# emonTx4-CTExt.net
KiCad netlist of a schematic drawn in EAGLE
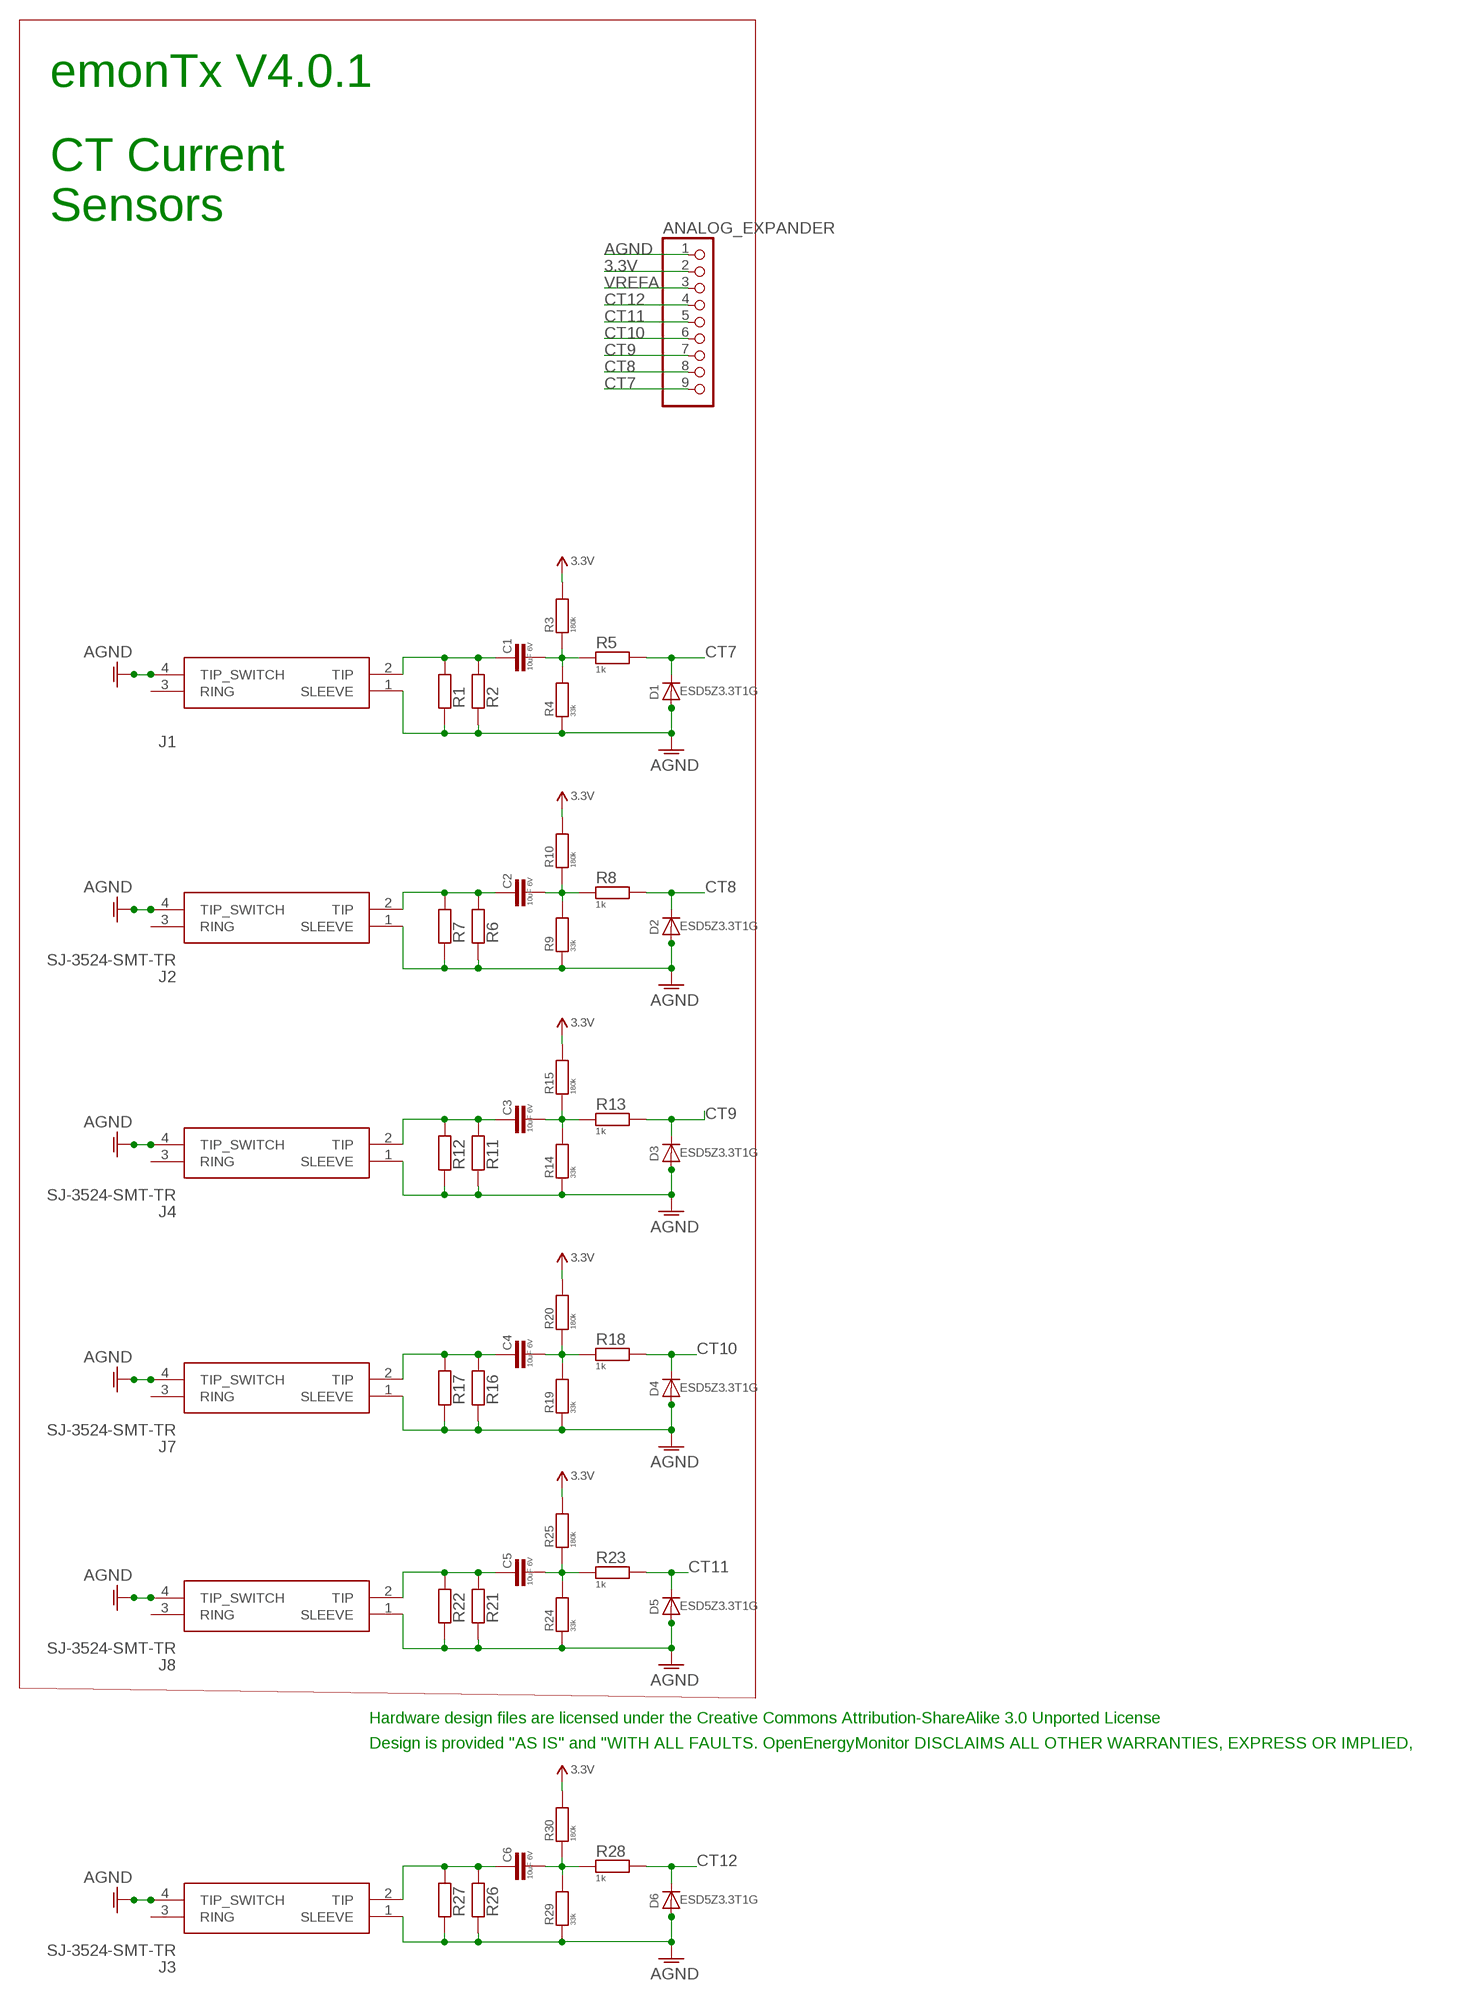
[diagram p0: schematic, sheet 1]

(export (version "E")
  (design (tool "Eeschema 10.0.6"))
  (components
    (comp (ref "ANALOG_EXPANDER")
      (value "PINHD-1X9")
      (footprint "eagle-import:1X09-BIG")
      (libsource (lib "eagle-import") (part "PINHD-1X9"))
    )
    (comp (ref "C1")
      (value "10uF 6V")
      (footprint "eagle-import:C0603")
      (libsource (lib "eagle-import") (part "C-EUC0603"))
    )
    (comp (ref "C2")
      (value "10uF 6V")
      (footprint "eagle-import:C0603")
      (libsource (lib "eagle-import") (part "C-EUC0603"))
    )
    (comp (ref "C3")
      (value "10uF 6V")
      (footprint "eagle-import:C0603")
      (libsource (lib "eagle-import") (part "C-EUC0603"))
    )
    (comp (ref "C4")
      (value "10uF 6V")
      (footprint "eagle-import:C0603")
      (libsource (lib "eagle-import") (part "C-EUC0603"))
    )
    (comp (ref "C5")
      (value "10uF 6V")
      (footprint "eagle-import:C0603")
      (libsource (lib "eagle-import") (part "C-EUC0603"))
    )
    (comp (ref "C6")
      (value "10uF 6V")
      (footprint "eagle-import:C0603")
      (libsource (lib "eagle-import") (part "C-EUC0603"))
    )
    (comp (ref "D1")
      (value "ESD5Z3.3T1G")
      (footprint "eagle-import:SOD-523")
      (libsource (lib "eagle-import") (part "DIODESOD-523"))
    )
    (comp (ref "D2")
      (value "ESD5Z3.3T1G")
      (footprint "eagle-import:SOD-523")
      (libsource (lib "eagle-import") (part "DIODESOD-523"))
    )
    (comp (ref "D3")
      (value "ESD5Z3.3T1G")
      (footprint "eagle-import:SOD-523")
      (libsource (lib "eagle-import") (part "DIODESOD-523"))
    )
    (comp (ref "D4")
      (value "ESD5Z3.3T1G")
      (footprint "eagle-import:SOD-523")
      (libsource (lib "eagle-import") (part "DIODESOD-523"))
    )
    (comp (ref "D5")
      (value "ESD5Z3.3T1G")
      (footprint "eagle-import:SOD-523")
      (libsource (lib "eagle-import") (part "DIODESOD-523"))
    )
    (comp (ref "D6")
      (value "ESD5Z3.3T1G")
      (footprint "eagle-import:SOD-523")
      (libsource (lib "eagle-import") (part "DIODESOD-523"))
    )
    (comp (ref "J1")
      (value "SJ-3524-SMT-TR")
      (footprint "eagle-import:SJ-3524-SMT-TR")
      (fields (field (name "MOUSER_PART_NUMBER") "490-SJ-3524-SMT-TR"))
      (libsource (lib "eagle-import") (part "SJ-3524-SMT-TR"))
    )
    (comp (ref "J2")
      (value "SJ-3524-SMT-TR")
      (footprint "eagle-import:SJ-3524-SMT-TR")
      (fields (field (name "MOUSER_PART_NUMBER") "490-SJ-3524-SMT-TR"))
      (libsource (lib "eagle-import") (part "SJ-3524-SMT-TR"))
    )
    (comp (ref "J3")
      (value "SJ-3524-SMT-TR")
      (footprint "eagle-import:SJ-3524-SMT-TR")
      (fields (field (name "MOUSER_PART_NUMBER") "490-SJ-3524-SMT-TR"))
      (libsource (lib "eagle-import") (part "SJ-3524-SMT-TR"))
    )
    (comp (ref "J4")
      (value "SJ-3524-SMT-TR")
      (footprint "eagle-import:SJ-3524-SMT-TR")
      (fields (field (name "MOUSER_PART_NUMBER") "490-SJ-3524-SMT-TR"))
      (libsource (lib "eagle-import") (part "SJ-3524-SMT-TR"))
    )
    (comp (ref "J7")
      (value "SJ-3524-SMT-TR")
      (footprint "eagle-import:SJ-3524-SMT-TR")
      (fields (field (name "MOUSER_PART_NUMBER") "490-SJ-3524-SMT-TR"))
      (libsource (lib "eagle-import") (part "SJ-3524-SMT-TR"))
    )
    (comp (ref "J8")
      (value "SJ-3524-SMT-TR")
      (footprint "eagle-import:SJ-3524-SMT-TR")
      (fields (field (name "MOUSER_PART_NUMBER") "490-SJ-3524-SMT-TR"))
      (libsource (lib "eagle-import") (part "SJ-3524-SMT-TR"))
    )
    (comp (ref "R1")
      (value "R-EU_R1206")
      (footprint "eagle-import:R1206")
      (libsource (lib "eagle-import") (part "R-EU_R1206"))
    )
    (comp (ref "R2")
      (value "R-EU_0204/7")
      (footprint "eagle-import:0204_7")
      (libsource (lib "eagle-import") (part "R-EU_0204/7"))
    )
    (comp (ref "R3")
      (value "180k")
      (footprint "eagle-import:R0603")
      (libsource (lib "eagle-import") (part "R-EU_R0603"))
    )
    (comp (ref "R4")
      (value "33k")
      (footprint "eagle-import:R0603")
      (libsource (lib "eagle-import") (part "R-EU_R0603"))
    )
    (comp (ref "R5")
      (value "1k")
      (footprint "eagle-import:R0603")
      (libsource (lib "eagle-import") (part "R-EU_R0603"))
    )
    (comp (ref "R6")
      (value "R-EU_0204/7")
      (footprint "eagle-import:0204_7")
      (libsource (lib "eagle-import") (part "R-EU_0204/7"))
    )
    (comp (ref "R7")
      (value "R-EU_R1206")
      (footprint "eagle-import:R1206")
      (libsource (lib "eagle-import") (part "R-EU_R1206"))
    )
    (comp (ref "R8")
      (value "1k")
      (footprint "eagle-import:R0603")
      (libsource (lib "eagle-import") (part "R-EU_R0603"))
    )
    (comp (ref "R9")
      (value "33k")
      (footprint "eagle-import:R0603")
      (libsource (lib "eagle-import") (part "R-EU_R0603"))
    )
    (comp (ref "R10")
      (value "180k")
      (footprint "eagle-import:R0603")
      (libsource (lib "eagle-import") (part "R-EU_R0603"))
    )
    (comp (ref "R11")
      (value "R-EU_0204/7")
      (footprint "eagle-import:0204_7")
      (libsource (lib "eagle-import") (part "R-EU_0204/7"))
    )
    (comp (ref "R12")
      (value "R-EU_R1206")
      (footprint "eagle-import:R1206")
      (libsource (lib "eagle-import") (part "R-EU_R1206"))
    )
    (comp (ref "R13")
      (value "1k")
      (footprint "eagle-import:R0603")
      (libsource (lib "eagle-import") (part "R-EU_R0603"))
    )
    (comp (ref "R14")
      (value "33k")
      (footprint "eagle-import:R0603")
      (libsource (lib "eagle-import") (part "R-EU_R0603"))
    )
    (comp (ref "R15")
      (value "180k")
      (footprint "eagle-import:R0603")
      (libsource (lib "eagle-import") (part "R-EU_R0603"))
    )
    (comp (ref "R16")
      (value "R-EU_0204/7")
      (footprint "eagle-import:0204_7")
      (libsource (lib "eagle-import") (part "R-EU_0204/7"))
    )
    (comp (ref "R17")
      (value "R-EU_R1206")
      (footprint "eagle-import:R1206")
      (libsource (lib "eagle-import") (part "R-EU_R1206"))
    )
    (comp (ref "R18")
      (value "1k")
      (footprint "eagle-import:R0603")
      (libsource (lib "eagle-import") (part "R-EU_R0603"))
    )
    (comp (ref "R19")
      (value "33k")
      (footprint "eagle-import:R0603")
      (libsource (lib "eagle-import") (part "R-EU_R0603"))
    )
    (comp (ref "R20")
      (value "180k")
      (footprint "eagle-import:R0603")
      (libsource (lib "eagle-import") (part "R-EU_R0603"))
    )
    (comp (ref "R21")
      (value "R-EU_0204/7")
      (footprint "eagle-import:0204_7")
      (libsource (lib "eagle-import") (part "R-EU_0204/7"))
    )
    (comp (ref "R22")
      (value "R-EU_R1206")
      (footprint "eagle-import:R1206")
      (libsource (lib "eagle-import") (part "R-EU_R1206"))
    )
    (comp (ref "R23")
      (value "1k")
      (footprint "eagle-import:R0603")
      (libsource (lib "eagle-import") (part "R-EU_R0603"))
    )
    (comp (ref "R24")
      (value "33k")
      (footprint "eagle-import:R0603")
      (libsource (lib "eagle-import") (part "R-EU_R0603"))
    )
    (comp (ref "R25")
      (value "180k")
      (footprint "eagle-import:R0603")
      (libsource (lib "eagle-import") (part "R-EU_R0603"))
    )
    (comp (ref "R26")
      (value "R-EU_0204/7")
      (footprint "eagle-import:0204_7")
      (libsource (lib "eagle-import") (part "R-EU_0204/7"))
    )
    (comp (ref "R27")
      (value "R-EU_R1206")
      (footprint "eagle-import:R1206")
      (libsource (lib "eagle-import") (part "R-EU_R1206"))
    )
    (comp (ref "R28")
      (value "1k")
      (footprint "eagle-import:R0603")
      (libsource (lib "eagle-import") (part "R-EU_R0603"))
    )
    (comp (ref "R29")
      (value "33k")
      (footprint "eagle-import:R0603")
      (libsource (lib "eagle-import") (part "R-EU_R0603"))
    )
    (comp (ref "R30")
      (value "180k")
      (footprint "eagle-import:R0603")
      (libsource (lib "eagle-import") (part "R-EU_R0603"))
    )
  )
  (nets
    (net (code "1") (name "/CT7") (class "Default")
      (node (ref "ANALOG_EXPANDER") (pin "9") (pinfunction "9_9") (pintype "passive"))
      (node (ref "D1") (pin "K") (pinfunction "C_K") (pintype "passive"))
      (node (ref "R5") (pin "2") (pinfunction "2_2") (pintype "passive"))
    )
    (net (code "2") (name "/CT8") (class "Default")
      (node (ref "ANALOG_EXPANDER") (pin "8") (pinfunction "8_8") (pintype "passive"))
      (node (ref "D2") (pin "K") (pinfunction "C_K") (pintype "passive"))
      (node (ref "R8") (pin "2") (pinfunction "2_2") (pintype "passive"))
    )
    (net (code "3") (name "/CT9") (class "Default")
      (node (ref "ANALOG_EXPANDER") (pin "7") (pinfunction "7_7") (pintype "passive"))
      (node (ref "D3") (pin "K") (pinfunction "C_K") (pintype "passive"))
      (node (ref "R13") (pin "2") (pinfunction "2_2") (pintype "passive"))
    )
    (net (code "4") (name "/CT10") (class "Default")
      (node (ref "ANALOG_EXPANDER") (pin "6") (pinfunction "6_6") (pintype "passive"))
      (node (ref "D4") (pin "K") (pinfunction "C_K") (pintype "passive"))
      (node (ref "R18") (pin "2") (pinfunction "2_2") (pintype "passive"))
    )
    (net (code "5") (name "/CT11") (class "Default")
      (node (ref "ANALOG_EXPANDER") (pin "5") (pinfunction "5_5") (pintype "passive"))
      (node (ref "D5") (pin "K") (pinfunction "C_K") (pintype "passive"))
      (node (ref "R23") (pin "2") (pinfunction "2_2") (pintype "passive"))
    )
    (net (code "6") (name "/CT12") (class "Default")
      (node (ref "ANALOG_EXPANDER") (pin "4") (pinfunction "4_4") (pintype "passive"))
      (node (ref "D6") (pin "K") (pinfunction "C_K") (pintype "passive"))
      (node (ref "R28") (pin "2") (pinfunction "2_2") (pintype "passive"))
    )
    (net (code "7") (name "/VREFA") (class "Default")
      (node (ref "ANALOG_EXPANDER") (pin "3") (pinfunction "3_3") (pintype "passive"))
    )
    (net (code "8") (name "3.3V") (class "Default")
      (node (ref "ANALOG_EXPANDER") (pin "2") (pinfunction "2_2") (pintype "passive"))
      (node (ref "R10") (pin "2") (pinfunction "2_2") (pintype "passive"))
      (node (ref "R15") (pin "2") (pinfunction "2_2") (pintype "passive"))
      (node (ref "R20") (pin "2") (pinfunction "2_2") (pintype "passive"))
      (node (ref "R25") (pin "2") (pinfunction "2_2") (pintype "passive"))
      (node (ref "R3") (pin "2") (pinfunction "2_2") (pintype "passive"))
      (node (ref "R30") (pin "2") (pinfunction "2_2") (pintype "passive"))
    )
    (net (code "9") (name "AGND") (class "Default")
      (node (ref "ANALOG_EXPANDER") (pin "1") (pinfunction "1_1") (pintype "passive"))
      (node (ref "D1") (pin "A") (pinfunction "A_A") (pintype "passive"))
      (node (ref "D2") (pin "A") (pinfunction "A_A") (pintype "passive"))
      (node (ref "D3") (pin "A") (pinfunction "A_A") (pintype "passive"))
      (node (ref "D4") (pin "A") (pinfunction "A_A") (pintype "passive"))
      (node (ref "D5") (pin "A") (pinfunction "A_A") (pintype "passive"))
      (node (ref "D6") (pin "A") (pinfunction "A_A") (pintype "passive"))
      (node (ref "J1") (pin "1") (pinfunction "SLEEVE_1") (pintype "bidirectional"))
      (node (ref "J1") (pin "4") (pinfunction "TIP_SWITCH_4") (pintype "bidirectional"))
      (node (ref "J2") (pin "1") (pinfunction "SLEEVE_1") (pintype "bidirectional"))
      (node (ref "J2") (pin "4") (pinfunction "TIP_SWITCH_4") (pintype "bidirectional"))
      (node (ref "J3") (pin "1") (pinfunction "SLEEVE_1") (pintype "bidirectional"))
      (node (ref "J3") (pin "4") (pinfunction "TIP_SWITCH_4") (pintype "bidirectional"))
      (node (ref "J4") (pin "1") (pinfunction "SLEEVE_1") (pintype "bidirectional"))
      (node (ref "J4") (pin "4") (pinfunction "TIP_SWITCH_4") (pintype "bidirectional"))
      (node (ref "J7") (pin "1") (pinfunction "SLEEVE_1") (pintype "bidirectional"))
      (node (ref "J7") (pin "4") (pinfunction "TIP_SWITCH_4") (pintype "bidirectional"))
      (node (ref "J8") (pin "1") (pinfunction "SLEEVE_1") (pintype "bidirectional"))
      (node (ref "J8") (pin "4") (pinfunction "TIP_SWITCH_4") (pintype "bidirectional"))
      (node (ref "R1") (pin "1") (pinfunction "1_1") (pintype "passive"))
      (node (ref "R11") (pin "1") (pinfunction "1_1") (pintype "passive"))
      (node (ref "R12") (pin "1") (pinfunction "1_1") (pintype "passive"))
      (node (ref "R14") (pin "2") (pinfunction "2_2") (pintype "passive"))
      (node (ref "R16") (pin "1") (pinfunction "1_1") (pintype "passive"))
      (node (ref "R17") (pin "1") (pinfunction "1_1") (pintype "passive"))
      (node (ref "R19") (pin "2") (pinfunction "2_2") (pintype "passive"))
      (node (ref "R2") (pin "1") (pinfunction "1_1") (pintype "passive"))
      (node (ref "R21") (pin "1") (pinfunction "1_1") (pintype "passive"))
      (node (ref "R22") (pin "1") (pinfunction "1_1") (pintype "passive"))
      (node (ref "R24") (pin "2") (pinfunction "2_2") (pintype "passive"))
      (node (ref "R26") (pin "1") (pinfunction "1_1") (pintype "passive"))
      (node (ref "R27") (pin "1") (pinfunction "1_1") (pintype "passive"))
      (node (ref "R29") (pin "2") (pinfunction "2_2") (pintype "passive"))
      (node (ref "R4") (pin "2") (pinfunction "2_2") (pintype "passive"))
      (node (ref "R6") (pin "1") (pinfunction "1_1") (pintype "passive"))
      (node (ref "R7") (pin "1") (pinfunction "1_1") (pintype "passive"))
      (node (ref "R9") (pin "2") (pinfunction "2_2") (pintype "passive"))
    )
    (net (code "10") (name "Net-(C1-Pad2)") (class "Default")
      (node (ref "C1") (pin "2") (pinfunction "2_2") (pintype "passive"))
      (node (ref "R3") (pin "1") (pinfunction "1_1") (pintype "passive"))
      (node (ref "R4") (pin "1") (pinfunction "1_1") (pintype "passive"))
      (node (ref "R5") (pin "1") (pinfunction "1_1") (pintype "passive"))
    )
    (net (code "11") (name "Net-(C2-Pad2)") (class "Default")
      (node (ref "C2") (pin "2") (pinfunction "2_2") (pintype "passive"))
      (node (ref "R10") (pin "1") (pinfunction "1_1") (pintype "passive"))
      (node (ref "R8") (pin "1") (pinfunction "1_1") (pintype "passive"))
      (node (ref "R9") (pin "1") (pinfunction "1_1") (pintype "passive"))
    )
    (net (code "12") (name "Net-(C3-Pad2)") (class "Default")
      (node (ref "C3") (pin "2") (pinfunction "2_2") (pintype "passive"))
      (node (ref "R13") (pin "1") (pinfunction "1_1") (pintype "passive"))
      (node (ref "R14") (pin "1") (pinfunction "1_1") (pintype "passive"))
      (node (ref "R15") (pin "1") (pinfunction "1_1") (pintype "passive"))
    )
    (net (code "13") (name "Net-(C4-Pad2)") (class "Default")
      (node (ref "C4") (pin "2") (pinfunction "2_2") (pintype "passive"))
      (node (ref "R18") (pin "1") (pinfunction "1_1") (pintype "passive"))
      (node (ref "R19") (pin "1") (pinfunction "1_1") (pintype "passive"))
      (node (ref "R20") (pin "1") (pinfunction "1_1") (pintype "passive"))
    )
    (net (code "14") (name "Net-(C5-Pad2)") (class "Default")
      (node (ref "C5") (pin "2") (pinfunction "2_2") (pintype "passive"))
      (node (ref "R23") (pin "1") (pinfunction "1_1") (pintype "passive"))
      (node (ref "R24") (pin "1") (pinfunction "1_1") (pintype "passive"))
      (node (ref "R25") (pin "1") (pinfunction "1_1") (pintype "passive"))
    )
    (net (code "15") (name "Net-(C6-Pad2)") (class "Default")
      (node (ref "C6") (pin "2") (pinfunction "2_2") (pintype "passive"))
      (node (ref "R28") (pin "1") (pinfunction "1_1") (pintype "passive"))
      (node (ref "R29") (pin "1") (pinfunction "1_1") (pintype "passive"))
      (node (ref "R30") (pin "1") (pinfunction "1_1") (pintype "passive"))
    )
    (net (code "16") (name "Net-(J1-TIP)") (class "Default")
      (node (ref "C1") (pin "1") (pinfunction "1_1") (pintype "passive"))
      (node (ref "J1") (pin "2") (pinfunction "TIP_2") (pintype "bidirectional"))
      (node (ref "R1") (pin "2") (pinfunction "2_2") (pintype "passive"))
      (node (ref "R2") (pin "2") (pinfunction "2_2") (pintype "passive"))
    )
    (net (code "17") (name "Net-(J2-TIP)") (class "Default")
      (node (ref "C2") (pin "1") (pinfunction "1_1") (pintype "passive"))
      (node (ref "J2") (pin "2") (pinfunction "TIP_2") (pintype "bidirectional"))
      (node (ref "R6") (pin "2") (pinfunction "2_2") (pintype "passive"))
      (node (ref "R7") (pin "2") (pinfunction "2_2") (pintype "passive"))
    )
    (net (code "18") (name "Net-(J3-TIP)") (class "Default")
      (node (ref "C6") (pin "1") (pinfunction "1_1") (pintype "passive"))
      (node (ref "J3") (pin "2") (pinfunction "TIP_2") (pintype "bidirectional"))
      (node (ref "R26") (pin "2") (pinfunction "2_2") (pintype "passive"))
      (node (ref "R27") (pin "2") (pinfunction "2_2") (pintype "passive"))
    )
    (net (code "19") (name "Net-(J4-TIP)") (class "Default")
      (node (ref "C3") (pin "1") (pinfunction "1_1") (pintype "passive"))
      (node (ref "J4") (pin "2") (pinfunction "TIP_2") (pintype "bidirectional"))
      (node (ref "R11") (pin "2") (pinfunction "2_2") (pintype "passive"))
      (node (ref "R12") (pin "2") (pinfunction "2_2") (pintype "passive"))
    )
    (net (code "20") (name "Net-(J7-TIP)") (class "Default")
      (node (ref "C4") (pin "1") (pinfunction "1_1") (pintype "passive"))
      (node (ref "J7") (pin "2") (pinfunction "TIP_2") (pintype "bidirectional"))
      (node (ref "R16") (pin "2") (pinfunction "2_2") (pintype "passive"))
      (node (ref "R17") (pin "2") (pinfunction "2_2") (pintype "passive"))
    )
    (net (code "21") (name "Net-(J8-TIP)") (class "Default")
      (node (ref "C5") (pin "1") (pinfunction "1_1") (pintype "passive"))
      (node (ref "J8") (pin "2") (pinfunction "TIP_2") (pintype "bidirectional"))
      (node (ref "R21") (pin "2") (pinfunction "2_2") (pintype "passive"))
      (node (ref "R22") (pin "2") (pinfunction "2_2") (pintype "passive"))
    )
    (net (code "22") (name "unconnected-(J1-RING-Pad3)") (class "Default")
      (node (ref "J1") (pin "3") (pinfunction "RING_3") (pintype "bidirectional"))
    )
    (net (code "23") (name "unconnected-(J2-RING-Pad3)") (class "Default")
      (node (ref "J2") (pin "3") (pinfunction "RING_3") (pintype "bidirectional"))
    )
    (net (code "24") (name "unconnected-(J3-RING-Pad3)") (class "Default")
      (node (ref "J3") (pin "3") (pinfunction "RING_3") (pintype "bidirectional"))
    )
    (net (code "25") (name "unconnected-(J4-RING-Pad3)") (class "Default")
      (node (ref "J4") (pin "3") (pinfunction "RING_3") (pintype "bidirectional"))
    )
    (net (code "26") (name "unconnected-(J7-RING-Pad3)") (class "Default")
      (node (ref "J7") (pin "3") (pinfunction "RING_3") (pintype "bidirectional"))
    )
    (net (code "27") (name "unconnected-(J8-RING-Pad3)") (class "Default")
      (node (ref "J8") (pin "3") (pinfunction "RING_3") (pintype "bidirectional"))
    )
  )
)
